# SparrowAprsArt.net
KiCad netlist of a schematic drawn in EAGLE
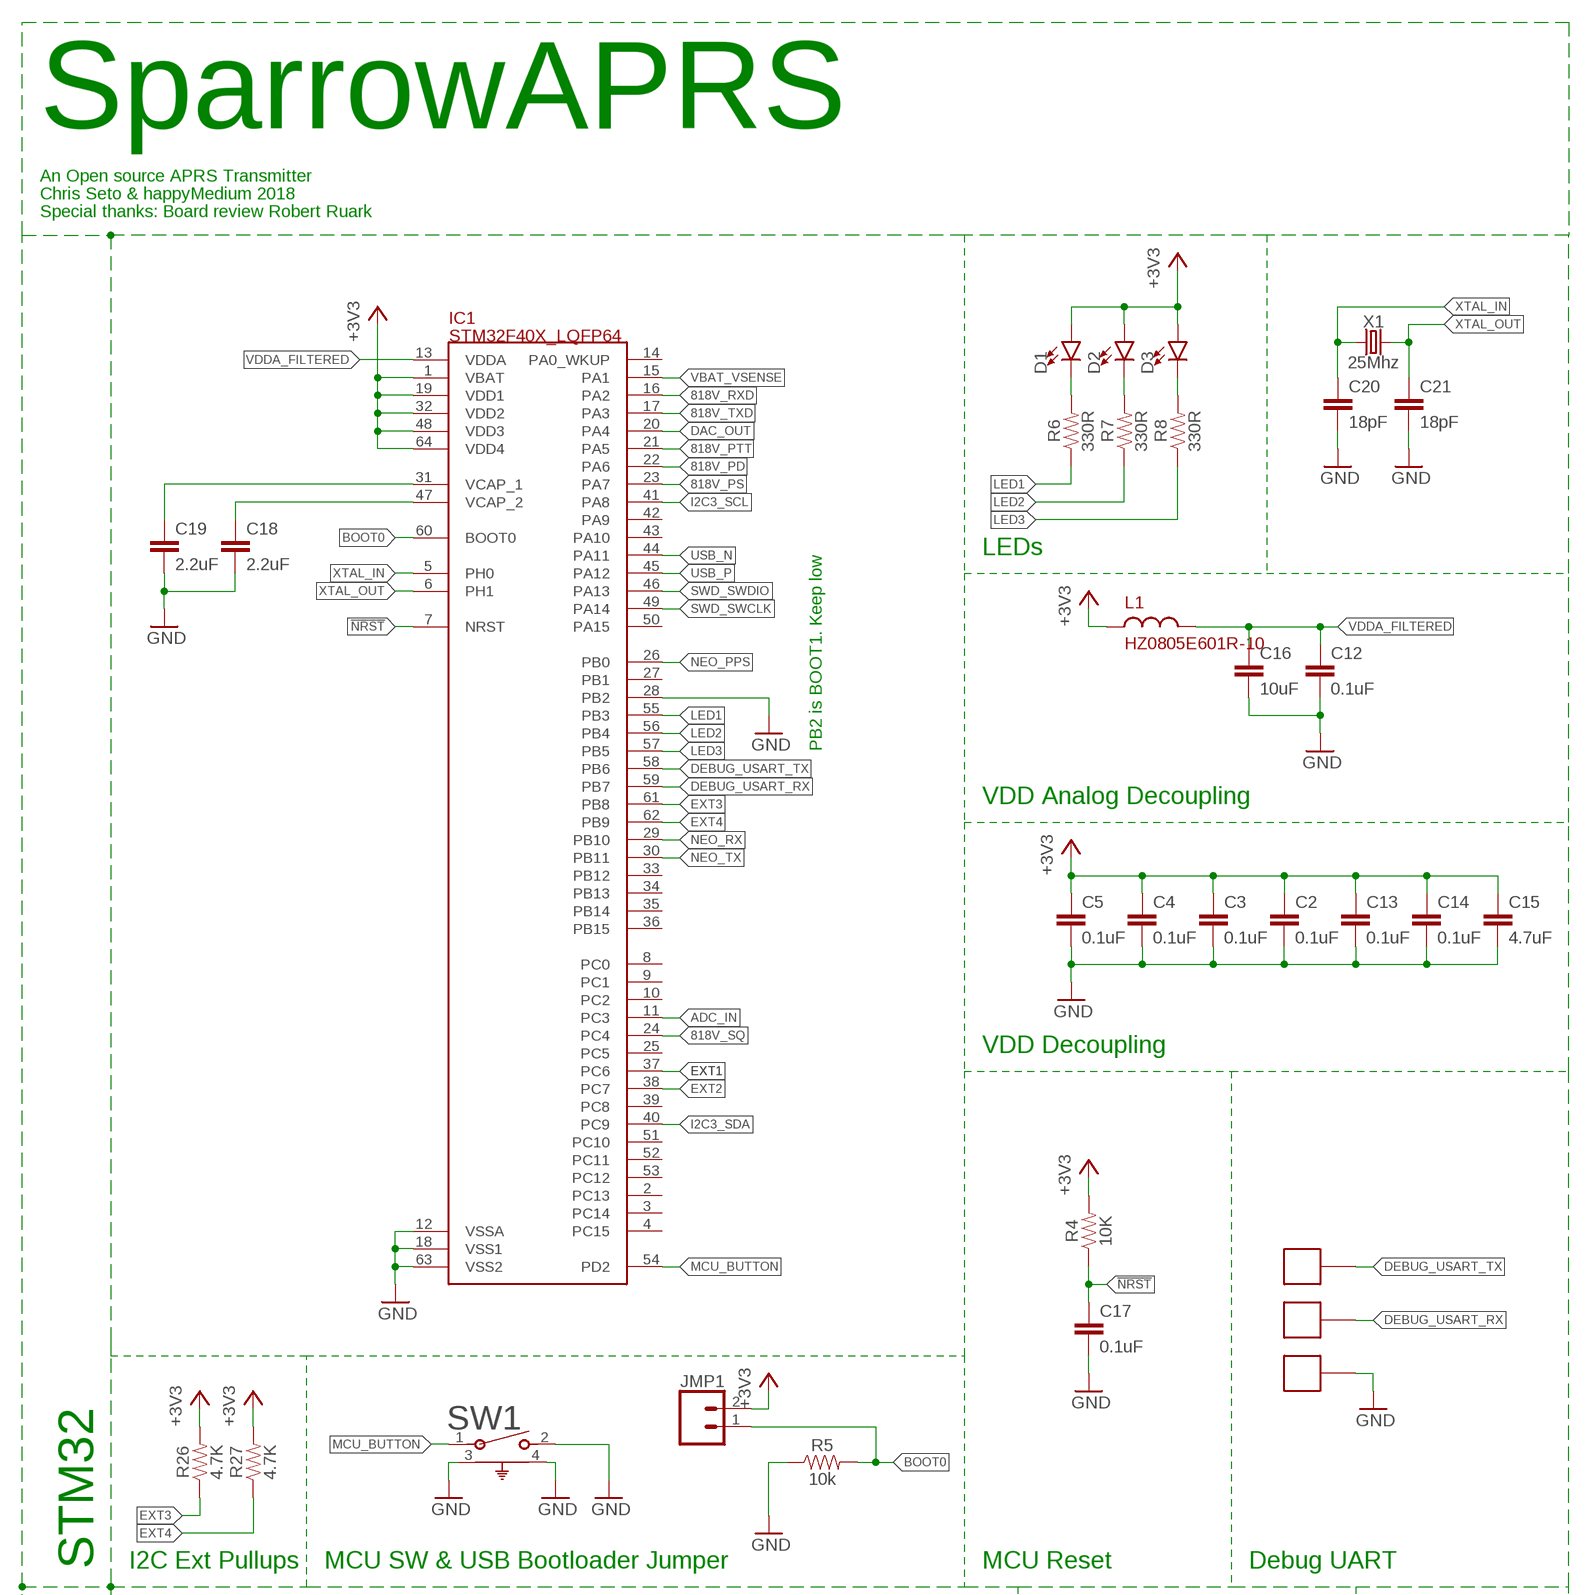
[diagram p0: schematic, sheet 1, part 1 of 2]
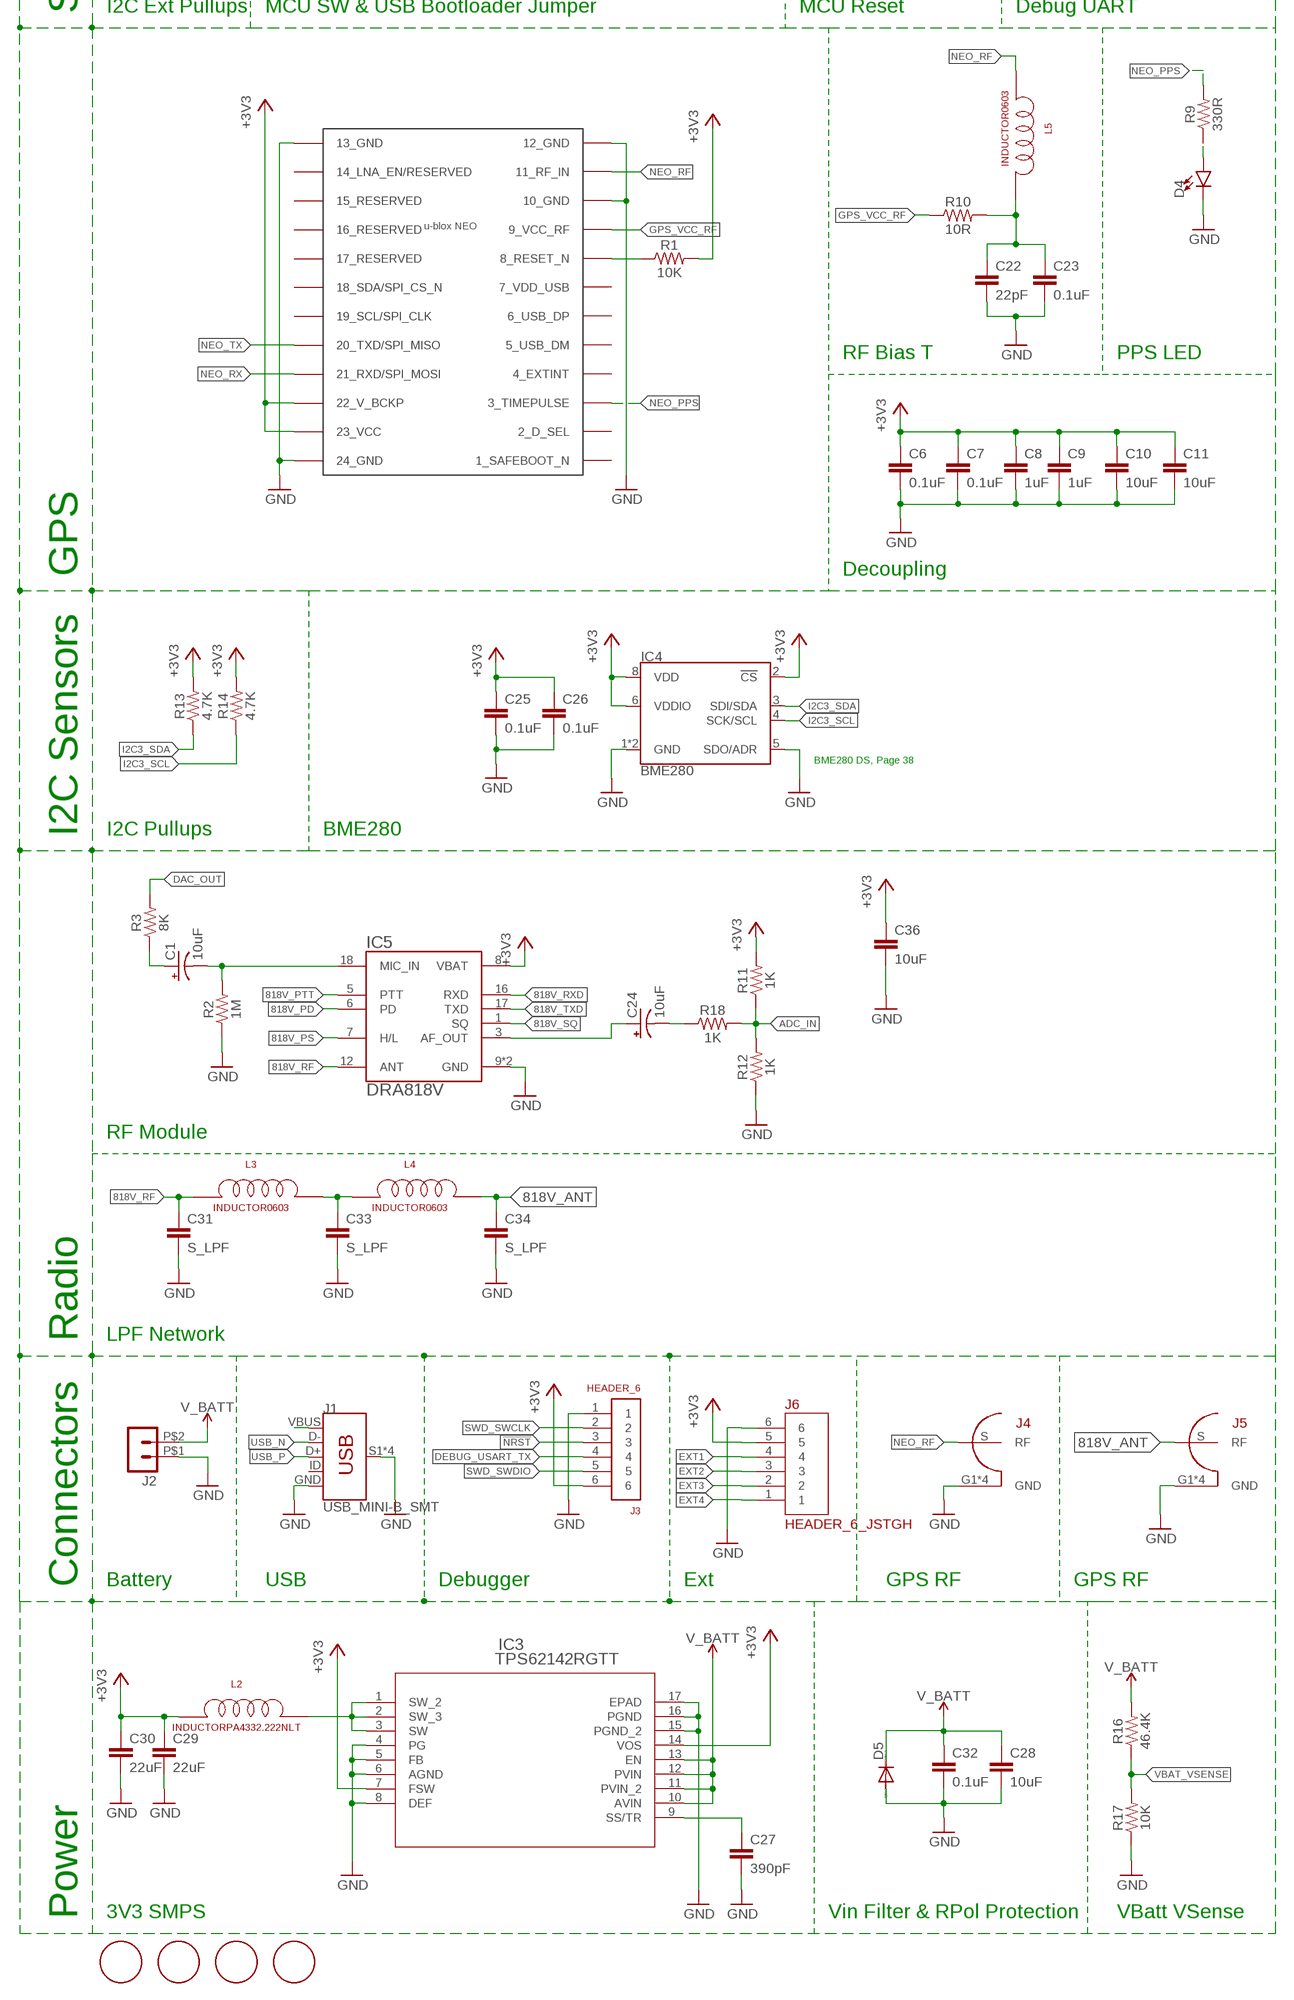
[diagram p1: schematic, sheet 1, part 2 of 2]

(export (version "E")
  (design (tool "Eeschema 10.0.6"))
  (components
    (comp (ref "C1")
      (value "10uF")
      (footprint "eagle-import:1206")
      (libsource (lib "eagle-import") (part "CAP_POL1206_POL"))
    )
    (comp (ref "C2")
      (value "0.1uF")
      (footprint "eagle-import:0603")
      (libsource (lib "eagle-import") (part "CAP0603"))
    )
    (comp (ref "C3")
      (value "0.1uF")
      (footprint "eagle-import:0603")
      (libsource (lib "eagle-import") (part "CAP0603"))
    )
    (comp (ref "C4")
      (value "0.1uF")
      (footprint "eagle-import:0603")
      (libsource (lib "eagle-import") (part "CAP0603"))
    )
    (comp (ref "C5")
      (value "0.1uF")
      (footprint "eagle-import:0603")
      (libsource (lib "eagle-import") (part "CAP0603"))
    )
    (comp (ref "C6")
      (value "0.1uF")
      (footprint "eagle-import:0603")
      (libsource (lib "eagle-import") (part "CAP0603"))
    )
    (comp (ref "C7")
      (value "0.1uF")
      (footprint "eagle-import:0603")
      (libsource (lib "eagle-import") (part "CAP0603"))
    )
    (comp (ref "C8")
      (value "1uF")
      (footprint "eagle-import:C0805")
      (libsource (lib "eagle-import") (part "C-EUC0805"))
    )
    (comp (ref "C9")
      (value "1uF")
      (footprint "eagle-import:C0805")
      (libsource (lib "eagle-import") (part "C-EUC0805"))
    )
    (comp (ref "C10")
      (value "10uF")
      (footprint "eagle-import:C0805")
      (libsource (lib "eagle-import") (part "C-EUC0805"))
    )
    (comp (ref "C11")
      (value "10uF")
      (footprint "eagle-import:C0805")
      (libsource (lib "eagle-import") (part "C-EUC0805"))
    )
    (comp (ref "C12")
      (value "0.1uF")
      (footprint "eagle-import:0603")
      (libsource (lib "eagle-import") (part "CAP0603"))
    )
    (comp (ref "C13")
      (value "0.1uF")
      (footprint "eagle-import:0603")
      (libsource (lib "eagle-import") (part "CAP0603"))
    )
    (comp (ref "C14")
      (value "0.1uF")
      (footprint "eagle-import:0603")
      (libsource (lib "eagle-import") (part "CAP0603"))
    )
    (comp (ref "C15")
      (value "4.7uF")
      (footprint "eagle-import:C0805")
      (libsource (lib "eagle-import") (part "C-EUC0805"))
    )
    (comp (ref "C16")
      (value "10uF")
      (footprint "eagle-import:C0805")
      (libsource (lib "eagle-import") (part "C-EUC0805"))
    )
    (comp (ref "C17")
      (value "0.1uF")
      (footprint "eagle-import:0603")
      (libsource (lib "eagle-import") (part "CAP0603"))
    )
    (comp (ref "C18")
      (value "2.2uF")
      (footprint "eagle-import:C0805")
      (libsource (lib "eagle-import") (part "C-EUC0805"))
    )
    (comp (ref "C19")
      (value "2.2uF")
      (footprint "eagle-import:C0805")
      (libsource (lib "eagle-import") (part "C-EUC0805"))
    )
    (comp (ref "C20")
      (value "18pF")
      (footprint "eagle-import:0603")
      (libsource (lib "eagle-import") (part "CAP0603"))
    )
    (comp (ref "C21")
      (value "18pF")
      (footprint "eagle-import:0603")
      (libsource (lib "eagle-import") (part "CAP0603"))
    )
    (comp (ref "C22")
      (value "22pF")
      (footprint "eagle-import:0603")
      (libsource (lib "eagle-import") (part "CAP0603"))
    )
    (comp (ref "C23")
      (value "0.1uF")
      (footprint "eagle-import:0603")
      (libsource (lib "eagle-import") (part "CAP0603"))
    )
    (comp (ref "C24")
      (value "10uF")
      (footprint "eagle-import:1206")
      (libsource (lib "eagle-import") (part "CAP_POL1206_POL"))
    )
    (comp (ref "C25")
      (value "0.1uF")
      (footprint "eagle-import:0603")
      (libsource (lib "eagle-import") (part "CAP0603"))
    )
    (comp (ref "C26")
      (value "0.1uF")
      (footprint "eagle-import:0603")
      (libsource (lib "eagle-import") (part "CAP0603"))
    )
    (comp (ref "C27")
      (value "390pF")
      (footprint "eagle-import:0603")
      (libsource (lib "eagle-import") (part "CAP0603"))
    )
    (comp (ref "C28")
      (value "10uF")
      (footprint "eagle-import:C0805")
      (libsource (lib "eagle-import") (part "C-EUC0805"))
    )
    (comp (ref "C29")
      (value "22uF")
      (footprint "eagle-import:1210")
      (libsource (lib "eagle-import") (part "CAP1210"))
    )
    (comp (ref "C30")
      (value "22uF")
      (footprint "eagle-import:1210")
      (libsource (lib "eagle-import") (part "CAP1210"))
    )
    (comp (ref "C31")
      (value "S_LPF")
      (footprint "eagle-import:0603")
      (libsource (lib "eagle-import") (part "CAP0603"))
    )
    (comp (ref "C32")
      (value "0.1uF")
      (footprint "eagle-import:0603")
      (libsource (lib "eagle-import") (part "CAP0603"))
    )
    (comp (ref "C33")
      (value "S_LPF")
      (footprint "eagle-import:0603")
      (libsource (lib "eagle-import") (part "CAP0603"))
    )
    (comp (ref "C34")
      (value "S_LPF")
      (footprint "eagle-import:0603")
      (libsource (lib "eagle-import") (part "CAP0603"))
    )
    (comp (ref "C36")
      (value "10uF")
      (footprint "eagle-import:C0805")
      (libsource (lib "eagle-import") (part "C-EUC0805"))
    )
    (comp (ref "D1")
      (value "LED0603")
      (footprint "eagle-import:LED-0603")
      (libsource (lib "eagle-import") (part "LED0603"))
    )
    (comp (ref "D2")
      (value "LED0603")
      (footprint "eagle-import:LED-0603")
      (libsource (lib "eagle-import") (part "LED0603"))
    )
    (comp (ref "D3")
      (value "LED0603")
      (footprint "eagle-import:LED-0603")
      (libsource (lib "eagle-import") (part "LED0603"))
    )
    (comp (ref "D4")
      (value "LED0603")
      (footprint "eagle-import:LED-0603")
      (libsource (lib "eagle-import") (part "LED0603"))
    )
    (comp (ref "D5")
      (value "DIODE-DO214AC")
      (footprint "eagle-import:DO214AC")
      (libsource (lib "eagle-import") (part "DIODE-DO214AC"))
    )
    (comp (ref "IC1")
      (value "STM32F40X_LQFP64")
      (footprint "eagle-import:STM32_LQFP64")
      (libsource (lib "eagle-import") (part "STM32F40X_LQFP64"))
    )
    (comp (ref "IC2")
      (value "NEO-M8")
      (footprint "eagle-import:NEO-M8")
      (libsource (lib "eagle-import") (part "NEO-M8"))
    )
    (comp (ref "IC3")
      (value "TPS62142RGTT")
      (footprint "eagle-import:RGT16_1P7X1P7")
      (libsource (lib "eagle-import") (part "TPS62142RGTT"))
    )
    (comp (ref "IC4")
      (value "BME280")
      (footprint "eagle-import:LGA-8-2.5X2.5")
      (libsource (lib "eagle-import") (part "BME280"))
    )
    (comp (ref "IC5")
      (value "DRA818V")
      (footprint "eagle-import:DORJI_DRA818V")
      (fields (field (name "MF") "DORJI"))
      (libsource (lib "eagle-import") (part "DRA818V"))
    )
    (comp (ref "J1")
      (value "USB_MINI-B_SMT")
      (footprint "eagle-import:USB-MINIB")
      (libsource (lib "eagle-import") (part "USB_MINI-B_SMT"))
    )
    (comp (ref "J2")
      (value "HEADER_POS2_43650-0200")
      (footprint "eagle-import:43650-0200")
      (libsource (lib "eagle-import") (part "HEADER_POS2_?43650-0200"))
    )
    (comp (ref "J3")
      (value "HEADER_6")
      (footprint "eagle-import:6X2_SMT")
      (libsource (lib "eagle-import") (part "HEADER_6"))
    )
    (comp (ref "J4")
      (value "FSK_RUARK2_SMA_0732511150")
      (footprint "eagle-import:FSK_RUARK2_WIDE_SMA")
      (libsource (lib "eagle-import") (part "FSK_RUARK2_SMA_0732511150"))
    )
    (comp (ref "J5")
      (value "FSK_RUARK2_SMA_0732511150")
      (footprint "eagle-import:FSK_RUARK2_WIDE_SMA")
      (libsource (lib "eagle-import") (part "FSK_RUARK2_SMA_0732511150"))
    )
    (comp (ref "J6")
      (value "HEADER_6_JSTGH")
      (footprint "eagle-import:BM06B-GHS-TBT(LF)(SN)(N)")
      (libsource (lib "eagle-import") (part "HEADER_6_JSTGH"))
    )
    (comp (ref "JMP1")
      (value "CONN_02")
      (footprint "eagle-import:1X02")
      (libsource (lib "eagle-import") (part "CONN_02"))
    )
    (comp (ref "L1")
      (value "HZ0805E601R-10")
      (footprint "eagle-import:R0805")
      (libsource (lib "eagle-import") (part "HZ0805E601R-10"))
    )
    (comp (ref "L2")
      (value "INDUCTORPA4332.222NLT")
      (footprint "eagle-import:PA4332.222NLT")
      (libsource (lib "eagle-import") (part "INDUCTORPA4332.222NLT"))
    )
    (comp (ref "L3")
      (value "INDUCTOR0603")
      (footprint "eagle-import:0603")
      (libsource (lib "eagle-import") (part "INDUCTOR0603"))
    )
    (comp (ref "L4")
      (value "INDUCTOR0603")
      (footprint "eagle-import:0603")
      (libsource (lib "eagle-import") (part "INDUCTOR0603"))
    )
    (comp (ref "L5")
      (value "INDUCTOR0603")
      (footprint "eagle-import:0603")
      (libsource (lib "eagle-import") (part "INDUCTOR0603"))
    )
    (comp (ref "R1")
      (value "10K")
      (footprint "eagle-import:0603")
      (libsource (lib "eagle-import") (part "RESISTOR0603"))
    )
    (comp (ref "R2")
      (value "1M")
      (footprint "eagle-import:0603")
      (libsource (lib "eagle-import") (part "RESISTOR0603"))
    )
    (comp (ref "R3")
      (value "8K")
      (footprint "eagle-import:0603")
      (libsource (lib "eagle-import") (part "RESISTOR0603"))
    )
    (comp (ref "R4")
      (value "10K")
      (footprint "eagle-import:0603")
      (libsource (lib "eagle-import") (part "RESISTOR0603"))
    )
    (comp (ref "R5")
      (value "10k")
      (footprint "eagle-import:0603")
      (libsource (lib "eagle-import") (part "RESISTOR0603"))
    )
    (comp (ref "R6")
      (value "330R")
      (footprint "eagle-import:0603")
      (libsource (lib "eagle-import") (part "RESISTOR0603"))
    )
    (comp (ref "R7")
      (value "330R")
      (footprint "eagle-import:0603")
      (libsource (lib "eagle-import") (part "RESISTOR0603"))
    )
    (comp (ref "R8")
      (value "330R")
      (footprint "eagle-import:0603")
      (libsource (lib "eagle-import") (part "RESISTOR0603"))
    )
    (comp (ref "R9")
      (value "330R")
      (footprint "eagle-import:0603")
      (libsource (lib "eagle-import") (part "RESISTOR0603"))
    )
    (comp (ref "R10")
      (value "10R")
      (footprint "eagle-import:0603")
      (libsource (lib "eagle-import") (part "RESISTOR0603"))
    )
    (comp (ref "R11")
      (value "1K")
      (footprint "eagle-import:0603")
      (libsource (lib "eagle-import") (part "RESISTOR0603"))
    )
    (comp (ref "R12")
      (value "1K")
      (footprint "eagle-import:0603")
      (libsource (lib "eagle-import") (part "RESISTOR0603"))
    )
    (comp (ref "R13")
      (value "4.7K")
      (footprint "eagle-import:0603")
      (libsource (lib "eagle-import") (part "RESISTOR0603"))
    )
    (comp (ref "R14")
      (value "4.7K")
      (footprint "eagle-import:0603")
      (libsource (lib "eagle-import") (part "RESISTOR0603"))
    )
    (comp (ref "R16")
      (value "46.4K")
      (footprint "eagle-import:0603")
      (libsource (lib "eagle-import") (part "RESISTOR0603"))
    )
    (comp (ref "R17")
      (value "10K")
      (footprint "eagle-import:0603")
      (libsource (lib "eagle-import") (part "RESISTOR0603"))
    )
    (comp (ref "R18")
      (value "1K")
      (footprint "eagle-import:0603")
      (libsource (lib "eagle-import") (part "RESISTOR0603"))
    )
    (comp (ref "R26")
      (value "4.7K")
      (footprint "eagle-import:0603")
      (libsource (lib "eagle-import") (part "RESISTOR0603"))
    )
    (comp (ref "R27")
      (value "4.7K")
      (footprint "eagle-import:0603")
      (libsource (lib "eagle-import") (part "RESISTOR0603"))
    )
    (comp (ref "SW1")
      (value "1825027-8")
      (footprint "eagle-import:SW2_1825027-C")
      (fields (field (name "MANUFACTURER_PART_NUMBER") "18250278"))
      (libsource (lib "eagle-import") (part "1825027-8"))
    )
    (comp (ref "U$2")
      (value "SINGLEPADMIDPAD")
      (footprint "eagle-import:MIDPAD")
      (libsource (lib "eagle-import") (part "SINGLEPADMIDPAD"))
    )
    (comp (ref "U$3")
      (value "SINGLEPADMIDPAD")
      (footprint "eagle-import:MIDPAD")
      (libsource (lib "eagle-import") (part "SINGLEPADMIDPAD"))
    )
    (comp (ref "U$4")
      (value "SINGLEPADMIDPAD")
      (footprint "eagle-import:MIDPAD")
      (libsource (lib "eagle-import") (part "SINGLEPADMIDPAD"))
    )
    (comp (ref "U$7")
      (value "MOUNTING_HOLE#2")
      (footprint "eagle-import:#2_CLEARANCE_HOLE")
      (libsource (lib "eagle-import") (part "MOUNTING_HOLE#2"))
    )
    (comp (ref "U$8")
      (value "MOUNTING_HOLE#2")
      (footprint "eagle-import:#2_CLEARANCE_HOLE")
      (libsource (lib "eagle-import") (part "MOUNTING_HOLE#2"))
    )
    (comp (ref "U$9")
      (value "MOUNTING_HOLE#2")
      (footprint "eagle-import:#2_CLEARANCE_HOLE")
      (libsource (lib "eagle-import") (part "MOUNTING_HOLE#2"))
    )
    (comp (ref "U$10")
      (value "MOUNTING_HOLE#2")
      (footprint "eagle-import:#2_CLEARANCE_HOLE")
      (libsource (lib "eagle-import") (part "MOUNTING_HOLE#2"))
    )
    (comp (ref "X1")
      (value "25Mhz")
      (footprint "eagle-import:CRYSTAL-SMD-3.2X2.5MM")
      (libsource (lib "eagle-import") (part "CRYSTALSMD-3.2X2.5"))
    )
  )
  (nets
    (net (code "1") (name "+3V3") (class "Default")
      (node (ref "C10") (pin "1") (pinfunction "1_1") (pintype "passive"))
      (node (ref "C11") (pin "1") (pinfunction "1_1") (pintype "passive"))
      (node (ref "C13") (pin "1") (pinfunction "1_1") (pintype "passive"))
      (node (ref "C14") (pin "1") (pinfunction "1_1") (pintype "passive"))
      (node (ref "C15") (pin "1") (pinfunction "1_1") (pintype "passive"))
      (node (ref "C2") (pin "1") (pinfunction "1_1") (pintype "passive"))
      (node (ref "C25") (pin "1") (pinfunction "1_1") (pintype "passive"))
      (node (ref "C26") (pin "1") (pinfunction "1_1") (pintype "passive"))
      (node (ref "C29") (pin "1") (pinfunction "1_1") (pintype "passive"))
      (node (ref "C3") (pin "1") (pinfunction "1_1") (pintype "passive"))
      (node (ref "C30") (pin "1") (pinfunction "1_1") (pintype "passive"))
      (node (ref "C36") (pin "1") (pinfunction "1_1") (pintype "passive"))
      (node (ref "C4") (pin "1") (pinfunction "1_1") (pintype "passive"))
      (node (ref "C5") (pin "1") (pinfunction "1_1") (pintype "passive"))
      (node (ref "C6") (pin "1") (pinfunction "1_1") (pintype "passive"))
      (node (ref "C7") (pin "1") (pinfunction "1_1") (pintype "passive"))
      (node (ref "C8") (pin "1") (pinfunction "1_1") (pintype "passive"))
      (node (ref "C9") (pin "1") (pinfunction "1_1") (pintype "passive"))
      (node (ref "D1") (pin "A") (pinfunction "A_A") (pintype "passive"))
      (node (ref "D2") (pin "A") (pinfunction "A_A") (pintype "passive"))
      (node (ref "D3") (pin "A") (pinfunction "A_A") (pintype "passive"))
      (node (ref "IC1") (pin "1") (pinfunction "VBAT_1") (pintype "bidirectional"))
      (node (ref "IC1") (pin "19") (pinfunction "VDD1_19") (pintype "bidirectional"))
      (node (ref "IC1") (pin "32") (pinfunction "VDD2_32") (pintype "bidirectional"))
      (node (ref "IC1") (pin "48") (pinfunction "VDD3_48") (pintype "bidirectional"))
      (node (ref "IC1") (pin "64") (pinfunction "VDD4_64") (pintype "bidirectional"))
      (node (ref "IC2") (pin "22") (pinfunction "22_V_BCKP_22") (pintype "bidirectional"))
      (node (ref "IC2") (pin "23") (pinfunction "23_VCC_23") (pintype "bidirectional"))
      (node (ref "IC3") (pin "14") (pinfunction "VOS_14") (pintype "input"))
      (node (ref "IC3") (pin "7") (pinfunction "FSW_7") (pintype "input"))
      (node (ref "IC4") (pin "2") (pinfunction "~{CS}_2") (pintype "bidirectional"))
      (node (ref "IC4") (pin "6") (pinfunction "VDDIO_6") (pintype "bidirectional"))
      (node (ref "IC4") (pin "8") (pinfunction "VDD_8") (pintype "bidirectional"))
      (node (ref "IC5") (pin "8") (pinfunction "VBAT_8") (pintype "power_in"))
      (node (ref "J3") (pin "6") (pinfunction "6_6") (pintype "bidirectional"))
      (node (ref "J6") (pin "5") (pinfunction "5_5") (pintype "bidirectional"))
      (node (ref "JMP1") (pin "2") (pinfunction "2_2") (pintype "passive"))
      (node (ref "L1") (pin "1") (pinfunction "1_1") (pintype "passive"))
      (node (ref "L2") (pin "1") (pinfunction "1_1") (pintype "power_in"))
      (node (ref "R1") (pin "2") (pinfunction "2_2") (pintype "passive"))
      (node (ref "R11") (pin "2") (pinfunction "2_2") (pintype "passive"))
      (node (ref "R13") (pin "2") (pinfunction "2_2") (pintype "passive"))
      (node (ref "R14") (pin "2") (pinfunction "2_2") (pintype "passive"))
      (node (ref "R26") (pin "2") (pinfunction "2_2") (pintype "passive"))
      (node (ref "R27") (pin "2") (pinfunction "2_2") (pintype "passive"))
      (node (ref "R4") (pin "2") (pinfunction "2_2") (pintype "passive"))
    )
    (net (code "2") (name "/~{NRST}") (class "Default")
      (node (ref "C17") (pin "1") (pinfunction "1_1") (pintype "passive"))
      (node (ref "IC1") (pin "7") (pinfunction "NRST_7") (pintype "bidirectional"))
      (node (ref "J3") (pin "3") (pinfunction "3_3") (pintype "bidirectional"))
      (node (ref "R4") (pin "1") (pinfunction "1_1") (pintype "passive"))
    )
    (net (code "3") (name "818V_ANT") (class "Default")
      (node (ref "C34") (pin "1") (pinfunction "1_1") (pintype "passive"))
      (node (ref "J5") (pin "S") (pinfunction "RF_S") (pintype "bidirectional"))
      (node (ref "L4") (pin "2") (pinfunction "2_2") (pintype "power_in"))
    )
    (net (code "4") (name "818V_PD") (class "Default")
      (node (ref "IC1") (pin "22") (pinfunction "PA6_22") (pintype "bidirectional"))
      (node (ref "IC5") (pin "6") (pinfunction "PD_6") (pintype "input"))
    )
    (net (code "5") (name "818V_PS") (class "Default")
      (node (ref "IC1") (pin "23") (pinfunction "PA7_23") (pintype "bidirectional"))
      (node (ref "IC5") (pin "7") (pinfunction "H/L_7") (pintype "input"))
    )
    (net (code "6") (name "818V_PTT") (class "Default")
      (node (ref "IC1") (pin "21") (pinfunction "PA5_21") (pintype "bidirectional"))
      (node (ref "IC5") (pin "5") (pinfunction "PTT_5") (pintype "input"))
    )
    (net (code "7") (name "818V_RF") (class "Default")
      (node (ref "C31") (pin "1") (pinfunction "1_1") (pintype "passive"))
      (node (ref "IC5") (pin "12") (pinfunction "ANT_12") (pintype "passive"))
      (node (ref "L3") (pin "1") (pinfunction "1_1") (pintype "power_in"))
    )
    (net (code "8") (name "818V_RXD") (class "Default")
      (node (ref "IC1") (pin "16") (pinfunction "PA2_16") (pintype "bidirectional"))
      (node (ref "IC5") (pin "16") (pinfunction "RXD_16") (pintype "input"))
    )
    (net (code "9") (name "818V_SQ") (class "Default")
      (node (ref "IC1") (pin "24") (pinfunction "PC4_24") (pintype "bidirectional"))
      (node (ref "IC5") (pin "1") (pinfunction "SQ_1") (pintype "output"))
    )
    (net (code "10") (name "818V_TXD") (class "Default")
      (node (ref "IC1") (pin "17") (pinfunction "PA3_17") (pintype "bidirectional"))
      (node (ref "IC5") (pin "17") (pinfunction "TXD_17") (pintype "output"))
    )
    (net (code "11") (name "ADC_IN") (class "Default")
      (node (ref "IC1") (pin "11") (pinfunction "PC3_11") (pintype "bidirectional"))
      (node (ref "R11") (pin "1") (pinfunction "1_1") (pintype "passive"))
      (node (ref "R12") (pin "2") (pinfunction "2_2") (pintype "passive"))
      (node (ref "R18") (pin "2") (pinfunction "2_2") (pintype "passive"))
    )
    (net (code "12") (name "BOOT0") (class "Default")
      (node (ref "IC1") (pin "60") (pinfunction "BOOT0_60") (pintype "bidirectional"))
      (node (ref "JMP1") (pin "1") (pinfunction "1_1") (pintype "passive"))
      (node (ref "R5") (pin "2") (pinfunction "2_2") (pintype "passive"))
    )
    (net (code "13") (name "DAC_OUT") (class "Default")
      (node (ref "IC1") (pin "20") (pinfunction "PA4_20") (pintype "bidirectional"))
      (node (ref "R3") (pin "2") (pinfunction "2_2") (pintype "passive"))
    )
    (net (code "14") (name "DEBUG_USART_RX") (class "Default")
      (node (ref "IC1") (pin "59") (pinfunction "PB7_59") (pintype "bidirectional"))
      (node (ref "U$3") (pin "1") (pinfunction "1_1") (pintype "bidirectional"))
    )
    (net (code "15") (name "DEBUG_USART_TX") (class "Default")
      (node (ref "IC1") (pin "58") (pinfunction "PB6_58") (pintype "bidirectional"))
      (node (ref "J3") (pin "4") (pinfunction "4_4") (pintype "bidirectional"))
      (node (ref "U$2") (pin "1") (pinfunction "1_1") (pintype "bidirectional"))
    )
    (net (code "16") (name "EXT1") (class "Default")
      (node (ref "IC1") (pin "37") (pinfunction "PC6_37") (pintype "bidirectional"))
      (node (ref "J6") (pin "4") (pinfunction "4_4") (pintype "bidirectional"))
    )
    (net (code "17") (name "EXT2") (class "Default")
      (node (ref "IC1") (pin "38") (pinfunction "PC7_38") (pintype "bidirectional"))
      (node (ref "J6") (pin "3") (pinfunction "3_3") (pintype "bidirectional"))
    )
    (net (code "18") (name "EXT3") (class "Default")
      (node (ref "IC1") (pin "61") (pinfunction "PB8_61") (pintype "bidirectional"))
      (node (ref "J6") (pin "2") (pinfunction "2_2") (pintype "bidirectional"))
      (node (ref "R26") (pin "1") (pinfunction "1_1") (pintype "passive"))
    )
    (net (code "19") (name "EXT4") (class "Default")
      (node (ref "IC1") (pin "62") (pinfunction "PB9_62") (pintype "bidirectional"))
      (node (ref "J6") (pin "1") (pinfunction "1_1") (pintype "bidirectional"))
      (node (ref "R27") (pin "1") (pinfunction "1_1") (pintype "passive"))
    )
    (net (code "20") (name "GND") (class "Default")
      (node (ref "C10") (pin "2") (pinfunction "2_2") (pintype "passive"))
      (node (ref "C11") (pin "2") (pinfunction "2_2") (pintype "passive"))
      (node (ref "C12") (pin "2") (pinfunction "2_2") (pintype "passive"))
      (node (ref "C13") (pin "2") (pinfunction "2_2") (pintype "passive"))
      (node (ref "C14") (pin "2") (pinfunction "2_2") (pintype "passive"))
      (node (ref "C15") (pin "2") (pinfunction "2_2") (pintype "passive"))
      (node (ref "C16") (pin "2") (pinfunction "2_2") (pintype "passive"))
      (node (ref "C17") (pin "2") (pinfunction "2_2") (pintype "passive"))
      (node (ref "C18") (pin "2") (pinfunction "2_2") (pintype "passive"))
      (node (ref "C19") (pin "2") (pinfunction "2_2") (pintype "passive"))
      (node (ref "C2") (pin "2") (pinfunction "2_2") (pintype "passive"))
      (node (ref "C20") (pin "2") (pinfunction "2_2") (pintype "passive"))
      (node (ref "C21") (pin "2") (pinfunction "2_2") (pintype "passive"))
      (node (ref "C22") (pin "2") (pinfunction "2_2") (pintype "passive"))
      (node (ref "C23") (pin "2") (pinfunction "2_2") (pintype "passive"))
      (node (ref "C25") (pin "2") (pinfunction "2_2") (pintype "passive"))
      (node (ref "C26") (pin "2") (pinfunction "2_2") (pintype "passive"))
      (node (ref "C27") (pin "2") (pinfunction "2_2") (pintype "passive"))
      (node (ref "C28") (pin "2") (pinfunction "2_2") (pintype "passive"))
      (node (ref "C29") (pin "2") (pinfunction "2_2") (pintype "passive"))
      (node (ref "C3") (pin "2") (pinfunction "2_2") (pintype "passive"))
      (node (ref "C30") (pin "2") (pinfunction "2_2") (pintype "passive"))
      (node (ref "C31") (pin "2") (pinfunction "2_2") (pintype "passive"))
      (node (ref "C32") (pin "2") (pinfunction "2_2") (pintype "passive"))
      (node (ref "C33") (pin "2") (pinfunction "2_2") (pintype "passive"))
      (node (ref "C34") (pin "2") (pinfunction "2_2") (pintype "passive"))
      (node (ref "C36") (pin "2") (pinfunction "2_2") (pintype "passive"))
      (node (ref "C4") (pin "2") (pinfunction "2_2") (pintype "passive"))
      (node (ref "C5") (pin "2") (pinfunction "2_2") (pintype "passive"))
      (node (ref "C6") (pin "2") (pinfunction "2_2") (pintype "passive"))
      (node (ref "C7") (pin "2") (pinfunction "2_2") (pintype "passive"))
      (node (ref "C8") (pin "2") (pinfunction "2_2") (pintype "passive"))
      (node (ref "C9") (pin "2") (pinfunction "2_2") (pintype "passive"))
      (node (ref "D4") (pin "C") (pinfunction "C_C") (pintype "passive"))
      (node (ref "D5") (pin "A") (pinfunction "A_A") (pintype "passive"))
      (node (ref "IC1") (pin "12") (pinfunction "VSSA_12") (pintype "bidirectional"))
      (node (ref "IC1") (pin "18") (pinfunction "VSS1_18") (pintype "bidirectional"))
      (node (ref "IC1") (pin "28") (pinfunction "PB2_28") (pintype "bidirectional"))
      (node (ref "IC1") (pin "63") (pinfunction "VSS2_63") (pintype "bidirectional"))
      (node (ref "IC2") (pin "10") (pinfunction "10_GND_10") (pintype "bidirectional"))
      (node (ref "IC2") (pin "12") (pinfunction "12_GND_12") (pintype "bidirectional"))
      (node (ref "IC2") (pin "13") (pinfunction "13_GND_13") (pintype "bidirectional"))
      (node (ref "IC2") (pin "24") (pinfunction "24_GND_24") (pintype "bidirectional"))
      (node (ref "IC3") (pin "15") (pinfunction "PGND_2_15") (pintype "power_in"))
      (node (ref "IC3") (pin "16") (pinfunction "PGND_16") (pintype "power_in"))
      (node (ref "IC3") (pin "17") (pinfunction "EPAD_17") (pintype "passive"))
      (node (ref "IC3") (pin "4") (pinfunction "PG_4") (pintype "output"))
      (node (ref "IC3") (pin "5") (pinfunction "FB_5") (pintype "input"))
      (node (ref "IC3") (pin "6") (pinfunction "AGND_6") (pintype "power_in"))
      (node (ref "IC3") (pin "8") (pinfunction "DEF_8") (pintype "input"))
      (node (ref "IC4") (pin "1") (pinfunction "GND_1") (pintype "bidirectional"))
      (node (ref "IC4") (pin "5") (pinfunction "SDO/ADR_5") (pintype "bidirectional"))
      (node (ref "IC4") (pin "7") (pinfunction "GND_7") (pintype "bidirectional"))
      (node (ref "IC5") (pin "10") (pinfunction "GND_10") (pintype "power_in"))
      (node (ref "IC5") (pin "9") (pinfunction "GND_9") (pintype "power_in"))
      (node (ref "J1") (pin "GND") (pinfunction "GND_GND") (pintype "power_in"))
      (node (ref "J1") (pin "S1") (pinfunction "SHIELD_S1") (pintype "bidirectional"))
      (node (ref "J1") (pin "S2") (pinfunction "SHIELD_S2") (pintype "bidirectional"))
      (node (ref "J1") (pin "S3") (pinfunction "SHIELD_S3") (pintype "bidirectional"))
      (node (ref "J1") (pin "S4") (pinfunction "SHIELD_S4") (pintype "bidirectional"))
      (node (ref "J2") (pin "P$1") (pinfunction "1_P$1") (pintype "passive"))
      (node (ref "J3") (pin "1") (pinfunction "1_1") (pintype "bidirectional"))
      (node (ref "J4") (pin "G1") (pinfunction "GND_G1") (pintype "bidirectional"))
      (node (ref "J4") (pin "G2") (pinfunction "GND_G2") (pintype "bidirectional"))
      (node (ref "J4") (pin "G3") (pinfunction "GND_G3") (pintype "bidirectional"))
      (node (ref "J4") (pin "G4") (pinfunction "GND_G4") (pintype "bidirectional"))
      (node (ref "J5") (pin "G1") (pinfunction "GND_G1") (pintype "bidirectional"))
      (node (ref "J5") (pin "G2") (pinfunction "GND_G2") (pintype "bidirectional"))
      (node (ref "J5") (pin "G3") (pinfunction "GND_G3") (pintype "bidirectional"))
      (node (ref "J5") (pin "G4") (pinfunction "GND_G4") (pintype "bidirectional"))
      (node (ref "J6") (pin "6") (pinfunction "6_6") (pintype "bidirectional"))
      (node (ref "R12") (pin "1") (pinfunction "1_1") (pintype "passive"))
      (node (ref "R17") (pin "1") (pinfunction "1_1") (pintype "passive"))
      (node (ref "R2") (pin "1") (pinfunction "1_1") (pintype "passive"))
      (node (ref "R5") (pin "1") (pinfunction "1_1") (pintype "passive"))
      (node (ref "SW1") (pin "2") (pinfunction "2_2") (pintype "passive"))
      (node (ref "SW1") (pin "3") (pinfunction "3_3") (pintype "passive"))
      (node (ref "SW1") (pin "4") (pinfunction "4_4") (pintype "passive"))
      (node (ref "U$4") (pin "1") (pinfunction "1_1") (pintype "bidirectional"))
    )
    (net (code "21") (name "GPS_VCC_RF") (class "Default")
      (node (ref "IC2") (pin "9") (pinfunction "9_VCC_RF_9") (pintype "bidirectional"))
      (node (ref "R10") (pin "1") (pinfunction "1_1") (pintype "passive"))
    )
    (net (code "22") (name "I2C3_SCL") (class "Default")
      (node (ref "IC1") (pin "41") (pinfunction "PA8_41") (pintype "bidirectional"))
      (node (ref "IC4") (pin "4") (pinfunction "SCK/SCL_4") (pintype "bidirectional"))
      (node (ref "R14") (pin "1") (pinfunction "1_1") (pintype "passive"))
    )
    (net (code "23") (name "I2C3_SDA") (class "Default")
      (node (ref "IC1") (pin "40") (pinfunction "PC9_40") (pintype "bidirectional"))
      (node (ref "IC4") (pin "3") (pinfunction "SDI/SDA_3") (pintype "bidirectional"))
      (node (ref "R13") (pin "1") (pinfunction "1_1") (pintype "passive"))
    )
    (net (code "24") (name "LED1") (class "Default")
      (node (ref "IC1") (pin "55") (pinfunction "PB3_55") (pintype "bidirectional"))
      (node (ref "R6") (pin "1") (pinfunction "1_1") (pintype "passive"))
    )
    (net (code "25") (name "LED2") (class "Default")
      (node (ref "IC1") (pin "56") (pinfunction "PB4_56") (pintype "bidirectional"))
      (node (ref "R7") (pin "1") (pinfunction "1_1") (pintype "passive"))
    )
    (net (code "26") (name "LED3") (class "Default")
      (node (ref "IC1") (pin "57") (pinfunction "PB5_57") (pintype "bidirectional"))
      (node (ref "R8") (pin "1") (pinfunction "1_1") (pintype "passive"))
    )
    (net (code "27") (name "MCU_BUTTON") (class "Default")
      (node (ref "IC1") (pin "54") (pinfunction "PD2_54") (pintype "bidirectional"))
      (node (ref "SW1") (pin "1") (pinfunction "1_1") (pintype "passive"))
    )
    (net (code "28") (name "NEO_PPS") (class "Default")
      (node (ref "IC1") (pin "26") (pinfunction "PB0_26") (pintype "bidirectional"))
      (node (ref "IC2") (pin "3") (pinfunction "3_TIMEPULSE_3") (pintype "bidirectional"))
      (node (ref "R9") (pin "2") (pinfunction "2_2") (pintype "passive"))
    )
    (net (code "29") (name "NEO_RF") (class "Default")
      (node (ref "IC2") (pin "11") (pinfunction "11_RF_IN_11") (pintype "bidirectional"))
      (node (ref "J4") (pin "S") (pinfunction "RF_S") (pintype "bidirectional"))
      (node (ref "L5") (pin "1") (pinfunction "1_1") (pintype "power_in"))
    )
    (net (code "30") (name "NEO_RX") (class "Default")
      (node (ref "IC1") (pin "29") (pinfunction "PB10_29") (pintype "bidirectional"))
      (node (ref "IC2") (pin "21") (pinfunction "21_RXD/SPI_MOSI_21") (pintype "bidirectional"))
    )
    (net (code "31") (name "NEO_TX") (class "Default")
      (node (ref "IC1") (pin "30") (pinfunction "PB11_30") (pintype "bidirectional"))
      (node (ref "IC2") (pin "20") (pinfunction "20_TXD/SPI_MISO_20") (pintype "bidirectional"))
    )
    (net (code "32") (name "Net-(C1-+)") (class "Default")
      (node (ref "C1") (pin "1") (pinfunction "+_1") (pintype "passive"))
      (node (ref "R3") (pin "1") (pinfunction "1_1") (pintype "passive"))
    )
    (net (code "33") (name "Net-(C1--)") (class "Default")
      (node (ref "C1") (pin "2") (pinfunction "-_2") (pintype "passive"))
      (node (ref "IC5") (pin "18") (pinfunction "MIC_IN_18") (pintype "input"))
      (node (ref "R2") (pin "2") (pinfunction "2_2") (pintype "passive"))
    )
    (net (code "34") (name "Net-(C22-Pad1)") (class "Default")
      (node (ref "C22") (pin "1") (pinfunction "1_1") (pintype "passive"))
      (node (ref "C23") (pin "1") (pinfunction "1_1") (pintype "passive"))
      (node (ref "L5") (pin "2") (pinfunction "2_2") (pintype "power_in"))
      (node (ref "R10") (pin "2") (pinfunction "2_2") (pintype "passive"))
    )
    (net (code "35") (name "Net-(C24-+)") (class "Default")
      (node (ref "C24") (pin "1") (pinfunction "+_1") (pintype "passive"))
      (node (ref "IC5") (pin "3") (pinfunction "AF_OUT_3") (pintype "output"))
    )
    (net (code "36") (name "Net-(C24--)") (class "Default")
      (node (ref "C24") (pin "2") (pinfunction "-_2") (pintype "passive"))
      (node (ref "R18") (pin "1") (pinfunction "1_1") (pintype "passive"))
    )
    (net (code "37") (name "Net-(C33-Pad1)") (class "Default")
      (node (ref "C33") (pin "1") (pinfunction "1_1") (pintype "passive"))
      (node (ref "L3") (pin "2") (pinfunction "2_2") (pintype "power_in"))
      (node (ref "L4") (pin "1") (pinfunction "1_1") (pintype "power_in"))
    )
    (net (code "38") (name "Net-(D1-PadC)") (class "Default")
      (node (ref "D1") (pin "C") (pinfunction "C_C") (pintype "passive"))
      (node (ref "R6") (pin "2") (pinfunction "2_2") (pintype "passive"))
    )
    (net (code "39") (name "Net-(D2-PadC)") (class "Default")
      (node (ref "D2") (pin "C") (pinfunction "C_C") (pintype "passive"))
      (node (ref "R7") (pin "2") (pinfunction "2_2") (pintype "passive"))
    )
    (net (code "40") (name "Net-(D3-PadC)") (class "Default")
      (node (ref "D3") (pin "C") (pinfunction "C_C") (pintype "passive"))
      (node (ref "R8") (pin "2") (pinfunction "2_2") (pintype "passive"))
    )
    (net (code "41") (name "Net-(D4-PadA)") (class "Default")
      (node (ref "D4") (pin "A") (pinfunction "A_A") (pintype "passive"))
      (node (ref "R9") (pin "1") (pinfunction "1_1") (pintype "passive"))
    )
    (net (code "42") (name "Net-(IC1-VCAP_1)") (class "Default")
      (node (ref "C19") (pin "1") (pinfunction "1_1") (pintype "passive"))
      (node (ref "IC1") (pin "31") (pinfunction "VCAP_1_31") (pintype "bidirectional"))
    )
    (net (code "43") (name "Net-(IC1-VCAP_2)") (class "Default")
      (node (ref "C18") (pin "1") (pinfunction "1_1") (pintype "passive"))
      (node (ref "IC1") (pin "47") (pinfunction "VCAP_2_47") (pintype "bidirectional"))
    )
    (net (code "44") (name "Net-(IC2-8_RESET_N)") (class "Default")
      (node (ref "IC2") (pin "8") (pinfunction "8_RESET_N_8") (pintype "bidirectional"))
      (node (ref "R1") (pin "1") (pinfunction "1_1") (pintype "passive"))
    )
    (net (code "45") (name "Net-(IC3-SS{slash}TR)") (class "Default")
      (node (ref "C27") (pin "1") (pinfunction "1_1") (pintype "passive"))
      (node (ref "IC3") (pin "9") (pinfunction "SS/TR_9") (pintype "input"))
    )
    (net (code "46") (name "Net-(IC3-SW)") (class "Default")
      (node (ref "IC3") (pin "1") (pinfunction "SW_2_1") (pintype "output"))
      (node (ref "IC3") (pin "2") (pinfunction "SW_3_2") (pintype "output"))
      (node (ref "IC3") (pin "3") (pinfunction "SW_3") (pintype "output"))
      (node (ref "L2") (pin "2") (pinfunction "2_2") (pintype "power_in"))
    )
    (net (code "47") (name "SWD_SWCLK") (class "Default")
      (node (ref "IC1") (pin "49") (pinfunction "PA14_49") (pintype "bidirectional"))
      (node (ref "J3") (pin "2") (pinfunction "2_2") (pintype "bidirectional"))
    )
    (net (code "48") (name "SWD_SWDIO") (class "Default")
      (node (ref "IC1") (pin "46") (pinfunction "PA13_46") (pintype "bidirectional"))
      (node (ref "J3") (pin "5") (pinfunction "5_5") (pintype "bidirectional"))
    )
    (net (code "49") (name "USB_N") (class "Default")
      (node (ref "IC1") (pin "44") (pinfunction "PA11_44") (pintype "bidirectional"))
      (node (ref "J1") (pin "D-") (pinfunction "D-_D-") (pintype "bidirectional"))
    )
    (net (code "50") (name "USB_P") (class "Default")
      (node (ref "IC1") (pin "45") (pinfunction "PA12_45") (pintype "bidirectional"))
      (node (ref "J1") (pin "D+") (pinfunction "D+_D+") (pintype "bidirectional"))
    )
    (net (code "51") (name "VBAT_VSENSE") (class "Default")
      (node (ref "IC1") (pin "15") (pinfunction "PA1_15") (pintype "bidirectional"))
      (node (ref "R16") (pin "1") (pinfunction "1_1") (pintype "passive"))
      (node (ref "R17") (pin "2") (pinfunction "2_2") (pintype "passive"))
    )
    (net (code "52") (name "VDDA_FILTERED") (class "Default")
      (node (ref "C12") (pin "1") (pinfunction "1_1") (pintype "passive"))
      (node (ref "C16") (pin "1") (pinfunction "1_1") (pintype "passive"))
      (node (ref "IC1") (pin "13") (pinfunction "VDDA_13") (pintype "bidirectional"))
      (node (ref "L1") (pin "2") (pinfunction "2_2") (pintype "passive"))
    )
    (net (code "53") (name "V_BATT") (class "Default")
      (node (ref "C28") (pin "1") (pinfunction "1_1") (pintype "passive"))
      (node (ref "C32") (pin "1") (pinfunction "1_1") (pintype "passive"))
      (node (ref "D5") (pin "C") (pinfunction "C_C") (pintype "passive"))
      (node (ref "IC3") (pin "10") (pinfunction "AVIN_10") (pintype "input"))
      (node (ref "IC3") (pin "11") (pinfunction "PVIN_2_11") (pintype "input"))
      (node (ref "IC3") (pin "12") (pinfunction "PVIN_12") (pintype "input"))
      (node (ref "IC3") (pin "13") (pinfunction "EN_13") (pintype "input"))
      (node (ref "J2") (pin "P$2") (pinfunction "2_P$2") (pintype "passive"))
      (node (ref "R16") (pin "2") (pinfunction "2_2") (pintype "passive"))
    )
    (net (code "54") (name "XTAL_IN") (class "Default")
      (node (ref "C20") (pin "1") (pinfunction "1_1") (pintype "passive"))
      (node (ref "IC1") (pin "5") (pinfunction "PH0_5") (pintype "bidirectional"))
      (node (ref "X1") (pin "1") (pinfunction "1_1") (pintype "passive"))
    )
    (net (code "55") (name "XTAL_OUT") (class "Default")
      (node (ref "C21") (pin "1") (pinfunction "1_1") (pintype "passive"))
      (node (ref "IC1") (pin "6") (pinfunction "PH1_6") (pintype "bidirectional"))
      (node (ref "X1") (pin "3") (pinfunction "2_3") (pintype "passive"))
    )
    (net (code "56") (name "unconnected-(IC1-PA0_WKUP-Pad14)") (class "Default")
      (node (ref "IC1") (pin "14") (pinfunction "PA0_WKUP_14") (pintype "bidirectional"))
    )
    (net (code "57") (name "unconnected-(IC1-PA9-Pad42)") (class "Default")
      (node (ref "IC1") (pin "42") (pinfunction "PA9_42") (pintype "bidirectional"))
    )
    (net (code "58") (name "unconnected-(IC1-PA10-Pad43)") (class "Default")
      (node (ref "IC1") (pin "43") (pinfunction "PA10_43") (pintype "bidirectional"))
    )
    (net (code "59") (name "unconnected-(IC1-PA15-Pad50)") (class "Default")
      (node (ref "IC1") (pin "50") (pinfunction "PA15_50") (pintype "bidirectional"))
    )
    (net (code "60") (name "unconnected-(IC1-PB1-Pad27)") (class "Default")
      (node (ref "IC1") (pin "27") (pinfunction "PB1_27") (pintype "bidirectional"))
    )
    (net (code "61") (name "unconnected-(IC1-PB12-Pad33)") (class "Default")
      (node (ref "IC1") (pin "33") (pinfunction "PB12_33") (pintype "bidirectional"))
    )
    (net (code "62") (name "unconnected-(IC1-PB13-Pad34)") (class "Default")
      (node (ref "IC1") (pin "34") (pinfunction "PB13_34") (pintype "bidirectional"))
    )
    (net (code "63") (name "unconnected-(IC1-PB14-Pad35)") (class "Default")
      (node (ref "IC1") (pin "35") (pinfunction "PB14_35") (pintype "bidirectional"))
    )
    (net (code "64") (name "unconnected-(IC1-PB15-Pad36)") (class "Default")
      (node (ref "IC1") (pin "36") (pinfunction "PB15_36") (pintype "bidirectional"))
    )
    (net (code "65") (name "unconnected-(IC1-PC0-Pad8)") (class "Default")
      (node (ref "IC1") (pin "8") (pinfunction "PC0_8") (pintype "bidirectional"))
    )
    (net (code "66") (name "unconnected-(IC1-PC1-Pad9)") (class "Default")
      (node (ref "IC1") (pin "9") (pinfunction "PC1_9") (pintype "bidirectional"))
    )
    (net (code "67") (name "unconnected-(IC1-PC2-Pad10)") (class "Default")
      (node (ref "IC1") (pin "10") (pinfunction "PC2_10") (pintype "bidirectional"))
    )
    (net (code "68") (name "unconnected-(IC1-PC5-Pad25)") (class "Default")
      (node (ref "IC1") (pin "25") (pinfunction "PC5_25") (pintype "bidirectional"))
    )
    (net (code "69") (name "unconnected-(IC1-PC8-Pad39)") (class "Default")
      (node (ref "IC1") (pin "39") (pinfunction "PC8_39") (pintype "bidirectional"))
    )
    (net (code "70") (name "unconnected-(IC1-PC10-Pad51)") (class "Default")
      (node (ref "IC1") (pin "51") (pinfunction "PC10_51") (pintype "bidirectional"))
    )
    (net (code "71") (name "unconnected-(IC1-PC11-Pad52)") (class "Default")
      (node (ref "IC1") (pin "52") (pinfunction "PC11_52") (pintype "bidirectional"))
    )
    (net (code "72") (name "unconnected-(IC1-PC12-Pad53)") (class "Default")
      (node (ref "IC1") (pin "53") (pinfunction "PC12_53") (pintype "bidirectional"))
    )
    (net (code "73") (name "unconnected-(IC1-PC13-Pad2)") (class "Default")
      (node (ref "IC1") (pin "2") (pinfunction "PC13_2") (pintype "bidirectional"))
    )
    (net (code "74") (name "unconnected-(IC1-PC14-Pad3)") (class "Default")
      (node (ref "IC1") (pin "3") (pinfunction "PC14_3") (pintype "bidirectional"))
    )
    (net (code "75") (name "unconnected-(IC1-PC15-Pad4)") (class "Default")
      (node (ref "IC1") (pin "4") (pinfunction "PC15_4") (pintype "bidirectional"))
    )
    (net (code "76") (name "unconnected-(IC2-1_SAFEBOOT_N-Pad1)") (class "Default")
      (node (ref "IC2") (pin "1") (pinfunction "1_SAFEBOOT_N_1") (pintype "bidirectional"))
    )
    (net (code "77") (name "unconnected-(IC2-2_D_SEL-Pad2)") (class "Default")
      (node (ref "IC2") (pin "2") (pinfunction "2_D_SEL_2") (pintype "bidirectional"))
    )
    (net (code "78") (name "unconnected-(IC2-4_EXTINT-Pad4)") (class "Default")
      (node (ref "IC2") (pin "4") (pinfunction "4_EXTINT_4") (pintype "bidirectional"))
    )
    (net (code "79") (name "unconnected-(IC2-5_USB_DM-Pad5)") (class "Default")
      (node (ref "IC2") (pin "5") (pinfunction "5_USB_DM_5") (pintype "bidirectional"))
    )
    (net (code "80") (name "unconnected-(IC2-6_USB_DP-Pad6)") (class "Default")
      (node (ref "IC2") (pin "6") (pinfunction "6_USB_DP_6") (pintype "bidirectional"))
    )
    (net (code "81") (name "unconnected-(IC2-7_VDD_USB-Pad7)") (class "Default")
      (node (ref "IC2") (pin "7") (pinfunction "7_VDD_USB_7") (pintype "bidirectional"))
    )
    (net (code "82") (name "unconnected-(IC2-14_LNA_EN{slash}RESERVED-Pad14)") (class "Default")
      (node (ref "IC2") (pin "14") (pinfunction "14_LNA_EN/RESERVED_14") (pintype "bidirectional"))
    )
    (net (code "83") (name "unconnected-(IC2-15_RESERVED-Pad15)") (class "Default")
      (node (ref "IC2") (pin "15") (pinfunction "15_RESERVED_15") (pintype "bidirectional"))
    )
    (net (code "84") (name "unconnected-(IC2-16_RESERVED-Pad16)") (class "Default")
      (node (ref "IC2") (pin "16") (pinfunction "16_RESERVED_16") (pintype "bidirectional"))
    )
    (net (code "85") (name "unconnected-(IC2-17_RESERVED-Pad17)") (class "Default")
      (node (ref "IC2") (pin "17") (pinfunction "17_RESERVED_17") (pintype "bidirectional"))
    )
    (net (code "86") (name "unconnected-(IC2-18_SDA{slash}SPI_CS_N-Pad18)") (class "Default")
      (node (ref "IC2") (pin "18") (pinfunction "18_SDA/SPI_CS_N_18") (pintype "bidirectional"))
    )
    (net (code "87") (name "unconnected-(IC2-19_SCL{slash}SPI_CLK-Pad19)") (class "Default")
      (node (ref "IC2") (pin "19") (pinfunction "19_SCL/SPI_CLK_19") (pintype "bidirectional"))
    )
    (net (code "88") (name "unconnected-(J1-PadID)") (class "Default")
      (node (ref "J1") (pin "ID") (pinfunction "ID_ID") (pintype "bidirectional"))
    )
    (net (code "89") (name "unconnected-(J1-PadVBUS)") (class "Default")
      (node (ref "J1") (pin "VBUS") (pinfunction "VBUS_VBUS") (pintype "power_in"))
    )
  )
)
